# ut_basketball_robot_mainboard_2018.net
KiCad netlist of a schematic drawn in Altium Designer
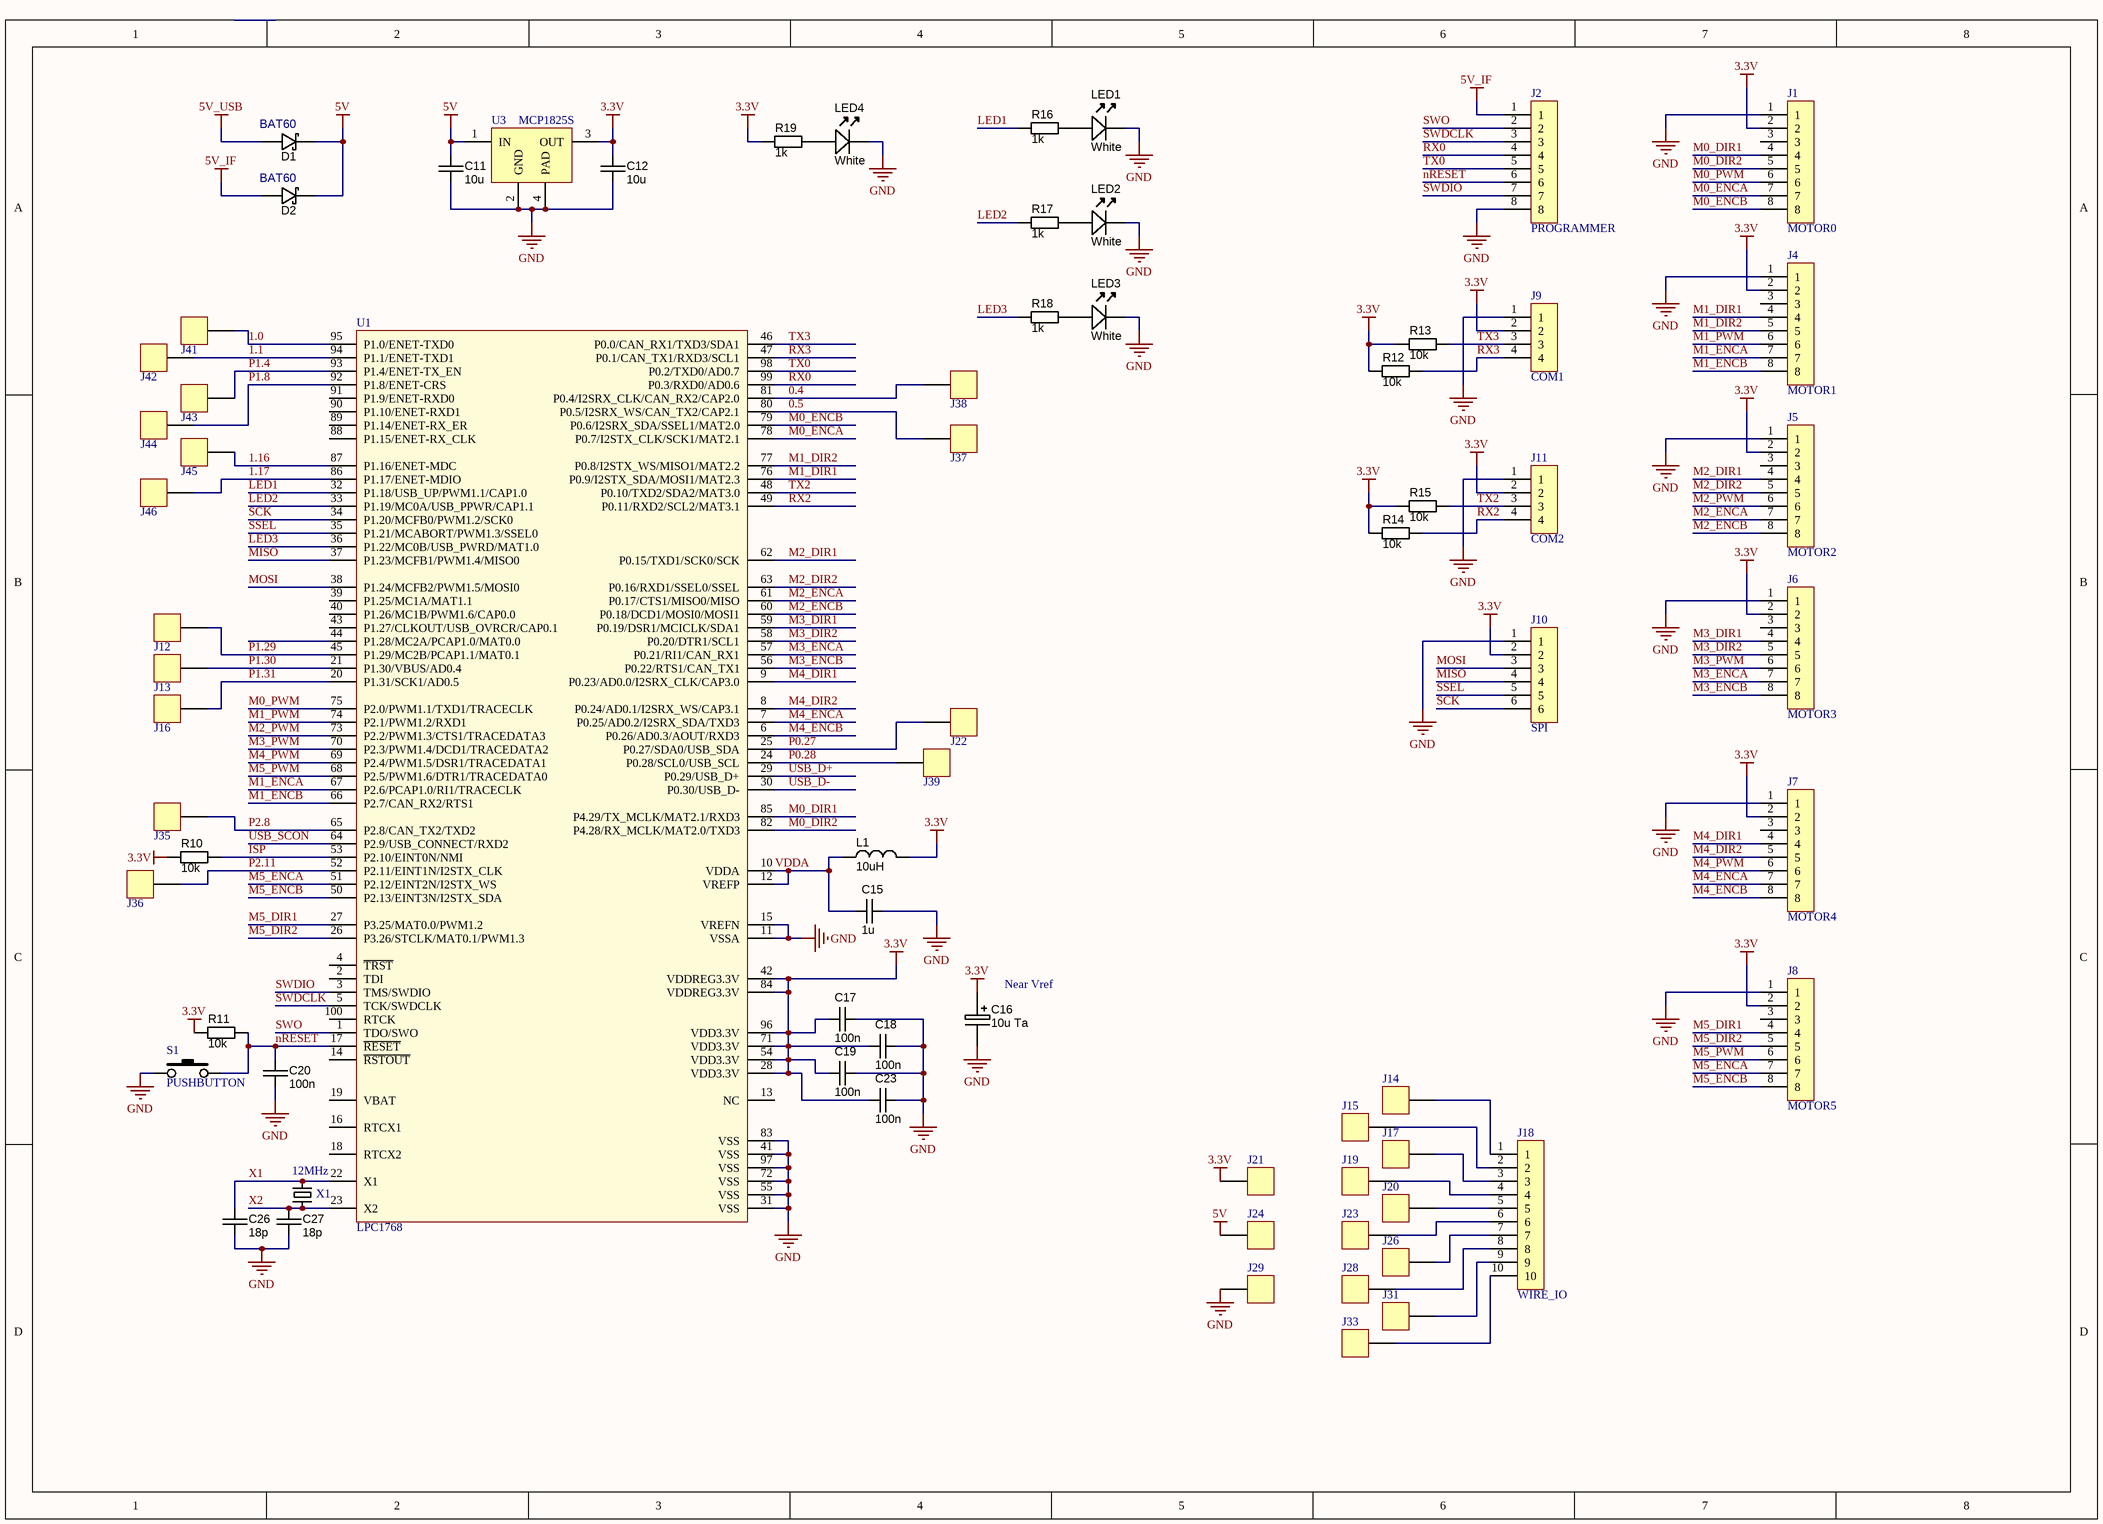
[diagram p0: ut_basketball_robot_mainboard_2018.SchDoc]

(export (version "E")
  (design (tool "Eeschema 10.0.6"))
  (components
    (comp (ref "C11")
      (value "10u")
      (footprint "CAPC3216X180N")
      (description "Capacitor SMD Cer 10uF 10% 10V X5R 1206")
      (fields (field (name "TOLERANCE") "±10%"))
      (libsource (lib "PBL - Capacitors") (part "CAPC_10u_1206_10V"))
    )
    (comp (ref "C12")
      (value "10u")
      (footprint "CAPC3216X180N")
      (description "Capacitor SMD Cer 10uF 10% 10V X5R 1206")
      (fields (field (name "TOLERANCE") "±10%"))
      (libsource (lib "PBL - Capacitors") (part "CAPC_10u_1206_10V"))
    )
    (comp (ref "C15")
      (value "1u")
      (footprint "CAPC1608X90N")
      (description "Capacitor SMD Cer 18pF 2% 100V NP0 0603")
      (fields (field (name "TOLERANCE") "±2%"))
      (libsource (lib "PBL - Capacitors") (part "CAPC_18p_0603_100V"))
    )
    (comp (ref "C16")
      (value "10u Ta")
      (footprint "CAPMP3528X210N")
      (description "Capacitor SMD Tantalum 47uF 20% 6.3V 1210")
      (fields (field (name "TOLERANCE") "±20%"))
      (libsource (lib "PBL - Capacitors") (part "CAPT_47u_1210_6V3"))
    )
    (comp (ref "C17")
      (value "100n")
      (footprint "CAPC1608X90N")
      (description "Capacitor SMD Cer 18pF 2% 100V NP0 0603")
      (fields (field (name "TOLERANCE") "±2%"))
      (libsource (lib "PBL - Capacitors") (part "CAPC_18p_0603_100V"))
    )
    (comp (ref "C18")
      (value "100n")
      (footprint "CAPC1608X90N")
      (description "Capacitor SMD Cer 18pF 2% 100V NP0 0603")
      (fields (field (name "TOLERANCE") "±2%"))
      (libsource (lib "PBL - Capacitors") (part "CAPC_18p_0603_100V"))
    )
    (comp (ref "C19")
      (value "100n")
      (footprint "CAPC1608X90N")
      (description "Capacitor SMD Cer 18pF 2% 100V NP0 0603")
      (fields (field (name "TOLERANCE") "±2%"))
      (libsource (lib "PBL - Capacitors") (part "CAPC_18p_0603_100V"))
    )
    (comp (ref "C20")
      (value "100n")
      (footprint "CAPC1608X90N")
      (description "Capacitor SMD Cer 18pF 2% 100V NP0 0603")
      (fields (field (name "TOLERANCE") "±2%"))
      (libsource (lib "PBL - Capacitors") (part "CAPC_18p_0603_100V"))
    )
    (comp (ref "C23")
      (value "100n")
      (footprint "CAPC1608X90N")
      (description "Capacitor SMD Cer 18pF 2% 100V NP0 0603")
      (fields (field (name "TOLERANCE") "±2%"))
      (libsource (lib "PBL - Capacitors") (part "CAPC_18p_0603_100V"))
    )
    (comp (ref "C26")
      (value "18p")
      (footprint "CAPC1608X90N")
      (description "Capacitor SMD Cer 18pF 2% 100V NP0 0603")
      (fields (field (name "TOLERANCE") "±2%"))
      (libsource (lib "PBL - Capacitors") (part "CAPC_18p_0603_100V"))
    )
    (comp (ref "C27")
      (value "18p")
      (footprint "CAPC1608X90N")
      (description "Capacitor SMD Cer 18pF 2% 100V NP0 0603")
      (fields (field (name "TOLERANCE") "±2%"))
      (libsource (lib "PBL - Capacitors") (part "CAPC_18p_0603_100V"))
    )
    (comp (ref "D1")
      (value "BAT60")
      (footprint "SOD323")
      (description "Diode Schottky SMD 20V 0.5A SOD123")
      (libsource (lib "PBL - Diodes") (part "DIODE_SCHOTTKY_SS0520"))
    )
    (comp (ref "D2")
      (value "BAT60")
      (footprint "SOD323")
      (description "Diode Schottky SMD 20V 0.5A SOD123")
      (libsource (lib "PBL - Diodes") (part "DIODE_SCHOTTKY_SS0520"))
    )
    (comp (ref "J1")
      (value "MOTOR0")
      (footprint "MICRO-MATCH-FOB-08")
      (libsource (lib "connectors_micromatch") (part "HEADER-8"))
    )
    (comp (ref "J2")
      (value "PROGRAMMER")
      (footprint "MICRO-MATCH-FOB-08")
      (libsource (lib "connectors_micromatch") (part "HEADER-8"))
    )
    (comp (ref "J4")
      (value "MOTOR1")
      (footprint "MICRO-MATCH-FOB-08")
      (libsource (lib "connectors_micromatch") (part "HEADER-8"))
    )
    (comp (ref "J5")
      (value "MOTOR2")
      (footprint "MICRO-MATCH-FOB-08")
      (libsource (lib "connectors_micromatch") (part "HEADER-8"))
    )
    (comp (ref "J6")
      (value "MOTOR3")
      (footprint "MICRO-MATCH-FOB-08")
      (libsource (lib "connectors_micromatch") (part "HEADER-8"))
    )
    (comp (ref "J7")
      (value "MOTOR4")
      (footprint "MICRO-MATCH-FOB-08")
      (libsource (lib "connectors_micromatch") (part "HEADER-8"))
    )
    (comp (ref "J8")
      (value "MOTOR5")
      (footprint "MICRO-MATCH-FOB-08")
      (libsource (lib "connectors_micromatch") (part "HEADER-8"))
    )
    (comp (ref "J9")
      (value "COM1")
      (footprint "MICRO-MATCH-FOB-04")
      (libsource (lib "connectors_micromatch") (part "HEADER-4"))
    )
    (comp (ref "J10")
      (value "SPI")
      (footprint "MICRO-MATCH-FOB-06")
      (libsource (lib "connectors_micromatch") (part "HEADER-6"))
    )
    (comp (ref "J11")
      (value "COM2")
      (footprint "MICRO-MATCH-FOB-04")
      (libsource (lib "connectors_micromatch") (part "HEADER-4"))
    )
    (comp (ref "J12")
      (value "HEADER-1")
      (footprint "PAD-1020")
      (libsource (lib "connectors") (part "HEADER-1"))
    )
    (comp (ref "J13")
      (value "HEADER-1")
      (footprint "PAD-1020")
      (libsource (lib "connectors") (part "HEADER-1"))
    )
    (comp (ref "J14")
      (value "HEADER-1")
      (footprint "PAD-1020")
      (libsource (lib "connectors") (part "HEADER-1"))
    )
    (comp (ref "J15")
      (value "HEADER-1")
      (footprint "PAD-1020")
      (libsource (lib "connectors") (part "HEADER-1"))
    )
    (comp (ref "J16")
      (value "HEADER-1")
      (footprint "PAD-1020")
      (libsource (lib "connectors") (part "HEADER-1"))
    )
    (comp (ref "J17")
      (value "HEADER-1")
      (footprint "PAD-1020")
      (libsource (lib "connectors") (part "HEADER-1"))
    )
    (comp (ref "J18")
      (value "WIRE_IO")
      (footprint "MICRO-MATCH-FOB-10")
      (libsource (lib "connectors_micromatch") (part "HEADER-10"))
    )
    (comp (ref "J19")
      (value "HEADER-1")
      (footprint "PAD-1020")
      (libsource (lib "connectors") (part "HEADER-1"))
    )
    (comp (ref "J20")
      (value "HEADER-1")
      (footprint "PAD-1020")
      (libsource (lib "connectors") (part "HEADER-1"))
    )
    (comp (ref "J21") (value "HEADER-1") (footprint "PAD-1020") (libsource (lib "") (part "HEADER-1_1")))
    (comp (ref "J22") (value "HEADER-1") (footprint "PAD-1020") (libsource (lib "") (part "HEADER-1_1")))
    (comp (ref "J23")
      (value "HEADER-1")
      (footprint "PAD-1020")
      (libsource (lib "connectors") (part "HEADER-1"))
    )
    (comp (ref "J24") (value "HEADER-1") (footprint "PAD-1020") (libsource (lib "") (part "HEADER-1_1")))
    (comp (ref "J26")
      (value "HEADER-1")
      (footprint "PAD-1020")
      (libsource (lib "connectors") (part "HEADER-1"))
    )
    (comp (ref "J28")
      (value "HEADER-1")
      (footprint "PAD-1020")
      (libsource (lib "connectors") (part "HEADER-1"))
    )
    (comp (ref "J29") (value "HEADER-1") (footprint "PAD-1020") (libsource (lib "") (part "HEADER-1_1")))
    (comp (ref "J31")
      (value "HEADER-1")
      (footprint "PAD-1020")
      (libsource (lib "connectors") (part "HEADER-1"))
    )
    (comp (ref "J33")
      (value "HEADER-1")
      (footprint "PAD-1020")
      (libsource (lib "connectors") (part "HEADER-1"))
    )
    (comp (ref "J35")
      (value "HEADER-1")
      (footprint "PAD-1020")
      (libsource (lib "connectors") (part "HEADER-1"))
    )
    (comp (ref "J36")
      (value "HEADER-1")
      (footprint "PAD-1020")
      (libsource (lib "connectors") (part "HEADER-1"))
    )
    (comp (ref "J37") (value "HEADER-1") (footprint "PAD-1020") (libsource (lib "") (part "HEADER-1_1")))
    (comp (ref "J38") (value "HEADER-1") (footprint "PAD-1020") (libsource (lib "") (part "HEADER-1_1")))
    (comp (ref "J39") (value "HEADER-1") (footprint "PAD-1020") (libsource (lib "") (part "HEADER-1_1")))
    (comp (ref "J41")
      (value "HEADER-1")
      (footprint "PAD-1020")
      (libsource (lib "connectors") (part "HEADER-1"))
    )
    (comp (ref "J42")
      (value "HEADER-1")
      (footprint "PAD-1020")
      (libsource (lib "connectors") (part "HEADER-1"))
    )
    (comp (ref "J43")
      (value "HEADER-1")
      (footprint "PAD-1020")
      (libsource (lib "connectors") (part "HEADER-1"))
    )
    (comp (ref "J44")
      (value "HEADER-1")
      (footprint "PAD-1020")
      (libsource (lib "connectors") (part "HEADER-1"))
    )
    (comp (ref "J45")
      (value "HEADER-1")
      (footprint "PAD-1020")
      (libsource (lib "connectors") (part "HEADER-1"))
    )
    (comp (ref "J46")
      (value "HEADER-1")
      (footprint "PAD-1020")
      (libsource (lib "connectors") (part "HEADER-1"))
    )
    (comp (ref "L1")
      (value "10uH")
      (footprint "INDC1608N")
      (description "Ferrite bead 120 Ohm at 100 MHz 2A 0603 SMD")
      (libsource (lib "PBL - Inductors") (part "FERRITE_120R-100MHz_0603"))
    )
    (comp (ref "LED1")
      (value "White")
      (footprint "LED-0603-WHITE")
      (description "LED 0603 SMD Bright White 8700K")
      (libsource (lib "PBL - Light Sources") (part "LED_SMD_White_0603_Bright"))
    )
    (comp (ref "LED2")
      (value "White")
      (footprint "LED-0603-WHITE")
      (description "LED 0603 SMD Bright White 8700K")
      (libsource (lib "PBL - Light Sources") (part "LED_SMD_White_0603_Bright"))
    )
    (comp (ref "LED3")
      (value "White")
      (footprint "LED-0603-WHITE")
      (description "LED 0603 SMD Bright White 8700K")
      (libsource (lib "PBL - Light Sources") (part "LED_SMD_White_0603_Bright"))
    )
    (comp (ref "LED4")
      (value "White")
      (footprint "LED-0603-WHITE")
      (description "LED 0603 SMD Bright White 8700K")
      (libsource (lib "PBL - Light Sources") (part "LED_SMD_White_0603_Bright"))
    )
    (comp (ref "R10")
      (value "10k")
      (footprint "RESC1608X55N")
      (description "Resistor SMD chip 10k Ohm 0.1W 5% 0603")
      (fields (field (name "TOLERANCE") "±5%"))
      (libsource (lib "") (part "RES_10K_0603_5%_1"))
    )
    (comp (ref "R11")
      (value "10k")
      (footprint "RESC1608X55N")
      (description "Resistor SMD chip 10k Ohm 0.1W 5% 0603")
      (fields (field (name "TOLERANCE") "±5%"))
      (libsource (lib "PBL - Resistors") (part "RES_10K_0603_5%"))
    )
    (comp (ref "R12")
      (value "10k")
      (footprint "RESC1608X55N")
      (description "Resistor SMD chip 10k Ohm 0.1W 5% 0603")
      (fields (field (name "TOLERANCE") "±5%"))
      (libsource (lib "PBL - Resistors") (part "RES_10K_0603_5%"))
    )
    (comp (ref "R13")
      (value "10k")
      (footprint "RESC1608X55N")
      (description "Resistor SMD chip 10k Ohm 0.1W 5% 0603")
      (fields (field (name "TOLERANCE") "±5%"))
      (libsource (lib "PBL - Resistors") (part "RES_10K_0603_5%"))
    )
    (comp (ref "R14")
      (value "10k")
      (footprint "RESC1608X55N")
      (description "Resistor SMD chip 10k Ohm 0.1W 5% 0603")
      (fields (field (name "TOLERANCE") "±5%"))
      (libsource (lib "PBL - Resistors") (part "RES_10K_0603_5%"))
    )
    (comp (ref "R15")
      (value "10k")
      (footprint "RESC1608X55N")
      (description "Resistor SMD chip 10k Ohm 0.1W 5% 0603")
      (fields (field (name "TOLERANCE") "±5%"))
      (libsource (lib "PBL - Resistors") (part "RES_10K_0603_5%"))
    )
    (comp (ref "R16")
      (value "1k")
      (footprint "RESC1608X55N")
      (description "Resistor SMD chip 120 Ohm 0.1W 5% 0603")
      (fields (field (name "TOLERANCE") "±5%"))
      (libsource (lib "PBL - Resistors") (part "RES_120R_0603_5%"))
    )
    (comp (ref "R17")
      (value "1k")
      (footprint "RESC1608X55N")
      (description "Resistor SMD chip 120 Ohm 0.1W 5% 0603")
      (fields (field (name "TOLERANCE") "±5%"))
      (libsource (lib "PBL - Resistors") (part "RES_120R_0603_5%"))
    )
    (comp (ref "R18")
      (value "1k")
      (footprint "RESC1608X55N")
      (description "Resistor SMD chip 120 Ohm 0.1W 5% 0603")
      (fields (field (name "TOLERANCE") "±5%"))
      (libsource (lib "PBL - Resistors") (part "RES_120R_0603_5%"))
    )
    (comp (ref "R19")
      (value "1k")
      (footprint "RESC1608X55N")
      (description "Resistor SMD chip 120 Ohm 0.1W 5% 0603")
      (fields (field (name "TOLERANCE") "±5%"))
      (libsource (lib "PBL - Resistors") (part "RES_120R_0603_5%"))
    )
    (comp (ref "S1")
      (value "PUSHBUTTON")
      (footprint "KMR421NGLFS")
      (libsource (lib "switches") (part "PUSHBUTTON"))
    )
    (comp (ref "U1") (value "LPC1768") (footprint "LQFP100") (libsource (lib "nxp") (part "LPC1768")))
    (comp (ref "U3")
      (value "MCP1825S")
      (footprint "SOT230P700X180-4N")
      (libsource (lib "power") (part "MIC5239"))
    )
    (comp (ref "X1")
      (value "12MHz")
      (footprint "XTAL-3.2x2.5")
      (libsource (lib "misc") (part "XTAL-3.2X2.5"))
    )
  )
  (nets
    (net (code "1") (name "/0.4") (class "Default")
      (node (ref "J38") (pin "1") (pinfunction "1_1") (pintype "passive"))
      (node (ref "U1") (pin "81") (pinfunction "P0.4/I2SRX_CLK/CAN_RX2/CAP2.0_81") (pintype "passive"))
    )
    (net (code "2") (name "/0.5") (class "Default")
      (node (ref "J37") (pin "1") (pinfunction "1_1") (pintype "passive"))
      (node (ref "U1") (pin "80") (pinfunction "P0.5/I2SRX_WS/CAN_TX2/CAP2.1_80") (pintype "passive"))
    )
    (net (code "3") (name "/1.0") (class "Default")
      (node (ref "J41") (pin "1") (pinfunction "1_1") (pintype "passive"))
      (node (ref "U1") (pin "95") (pinfunction "P1.0/ENET-TXD0_95") (pintype "passive"))
    )
    (net (code "4") (name "/1.1") (class "Default")
      (node (ref "J42") (pin "1") (pinfunction "1_1") (pintype "passive"))
      (node (ref "U1") (pin "94") (pinfunction "P1.1/ENET-TXD1_94") (pintype "passive"))
    )
    (net (code "5") (name "/1.16") (class "Default")
      (node (ref "J45") (pin "1") (pinfunction "1_1") (pintype "passive"))
      (node (ref "U1") (pin "87") (pinfunction "P1.16/ENET-MDC_87") (pintype "passive"))
    )
    (net (code "6") (name "/1.17") (class "Default")
      (node (ref "J46") (pin "1") (pinfunction "1_1") (pintype "passive"))
      (node (ref "U1") (pin "86") (pinfunction "P1.17/ENET-MDIO_86") (pintype "passive"))
    )
    (net (code "7") (name "/ISP") (class "Default")
      (node (ref "R10") (pin "1") (pinfunction "1_1") (pintype "passive"))
      (node (ref "U1") (pin "53") (pinfunction "P2.10/EINT0N/NMI_53") (pintype "passive"))
    )
    (net (code "8") (name "/LED1") (class "Default")
      (node (ref "R16") (pin "2") (pinfunction "2_2") (pintype "passive"))
      (node (ref "U1") (pin "32") (pinfunction "P1.18/USB_UP/PWM1.1/CAP1.0_32") (pintype "passive"))
    )
    (net (code "9") (name "/LED2") (class "Default")
      (node (ref "R17") (pin "2") (pinfunction "2_2") (pintype "passive"))
      (node (ref "U1") (pin "33") (pinfunction "P1.19/MC0A/USB_PPWR/CAP1.1_33") (pintype "passive"))
    )
    (net (code "10") (name "/LED3") (class "Default")
      (node (ref "R18") (pin "2") (pinfunction "2_2") (pintype "passive"))
      (node (ref "U1") (pin "36") (pinfunction "P1.22/MC0B/USB_PWRD/MAT1.0_36") (pintype "passive"))
    )
    (net (code "11") (name "/M0_DIR1") (class "Default")
      (node (ref "J1") (pin "4") (pinfunction "4_4") (pintype "passive"))
      (node (ref "U1") (pin "85") (pinfunction "P4.29/TX_MCLK/MAT2.1/RXD3_85") (pintype "passive"))
    )
    (net (code "12") (name "/M0_DIR2") (class "Default")
      (node (ref "J1") (pin "5") (pinfunction "5_5") (pintype "passive"))
      (node (ref "U1") (pin "82") (pinfunction "P4.28/RX_MCLK/MAT2.0/TXD3_82") (pintype "passive"))
    )
    (net (code "13") (name "/M0_ENCA") (class "Default")
      (node (ref "J1") (pin "7") (pinfunction "7_7") (pintype "passive"))
      (node (ref "U1") (pin "78") (pinfunction "P0.7/I2STX_CLK/SCK1/MAT2.1_78") (pintype "passive"))
    )
    (net (code "14") (name "/M0_ENCB") (class "Default")
      (node (ref "J1") (pin "8") (pinfunction "8_8") (pintype "passive"))
      (node (ref "U1") (pin "79") (pinfunction "P0.6/I2SRX_SDA/SSEL1/MAT2.0_79") (pintype "passive"))
    )
    (net (code "15") (name "/M0_PWM") (class "Default")
      (node (ref "J1") (pin "6") (pinfunction "6_6") (pintype "passive"))
      (node (ref "U1") (pin "75") (pinfunction "P2.0/PWM1.1/TXD1/TRACECLK_75") (pintype "passive"))
    )
    (net (code "16") (name "/M1_DIR1") (class "Default")
      (node (ref "J4") (pin "4") (pinfunction "4_4") (pintype "passive"))
      (node (ref "U1") (pin "76") (pinfunction "P0.9/I2STX_SDA/MOSI1/MAT2.3_76") (pintype "passive"))
    )
    (net (code "17") (name "/M1_DIR2") (class "Default")
      (node (ref "J4") (pin "5") (pinfunction "5_5") (pintype "passive"))
      (node (ref "U1") (pin "77") (pinfunction "P0.8/I2STX_WS/MISO1/MAT2.2_77") (pintype "passive"))
    )
    (net (code "18") (name "/M1_ENCA") (class "Default")
      (node (ref "J4") (pin "7") (pinfunction "7_7") (pintype "passive"))
      (node (ref "U1") (pin "67") (pinfunction "P2.6/PCAP1.0/RI1/TRACECLK_67") (pintype "passive"))
    )
    (net (code "19") (name "/M1_ENCB") (class "Default")
      (node (ref "J4") (pin "8") (pinfunction "8_8") (pintype "passive"))
      (node (ref "U1") (pin "66") (pinfunction "P2.7/CAN_RX2/RTS1_66") (pintype "passive"))
    )
    (net (code "20") (name "/M1_PWM") (class "Default")
      (node (ref "J4") (pin "6") (pinfunction "6_6") (pintype "passive"))
      (node (ref "U1") (pin "74") (pinfunction "P2.1/PWM1.2/RXD1_74") (pintype "passive"))
    )
    (net (code "21") (name "/M2_DIR1") (class "Default")
      (node (ref "J5") (pin "4") (pinfunction "4_4") (pintype "passive"))
      (node (ref "U1") (pin "62") (pinfunction "P0.15/TXD1/SCK0/SCK_62") (pintype "passive"))
    )
    (net (code "22") (name "/M2_DIR2") (class "Default")
      (node (ref "J5") (pin "5") (pinfunction "5_5") (pintype "passive"))
      (node (ref "U1") (pin "63") (pinfunction "P0.16/RXD1/SSEL0/SSEL_63") (pintype "passive"))
    )
    (net (code "23") (name "/M2_ENCA") (class "Default")
      (node (ref "J5") (pin "7") (pinfunction "7_7") (pintype "passive"))
      (node (ref "U1") (pin "61") (pinfunction "P0.17/CTS1/MISO0/MISO_61") (pintype "passive"))
    )
    (net (code "24") (name "/M2_ENCB") (class "Default")
      (node (ref "J5") (pin "8") (pinfunction "8_8") (pintype "passive"))
      (node (ref "U1") (pin "60") (pinfunction "P0.18/DCD1/MOSI0/MOSI1_60") (pintype "passive"))
    )
    (net (code "25") (name "/M2_PWM") (class "Default")
      (node (ref "J5") (pin "6") (pinfunction "6_6") (pintype "passive"))
      (node (ref "U1") (pin "73") (pinfunction "P2.2/PWM1.3/CTS1/TRACEDATA3_73") (pintype "passive"))
    )
    (net (code "26") (name "/M3_DIR1") (class "Default")
      (node (ref "J6") (pin "4") (pinfunction "4_4") (pintype "passive"))
      (node (ref "U1") (pin "59") (pinfunction "P0.19/DSR1/MCICLK/SDA1_59") (pintype "passive"))
    )
    (net (code "27") (name "/M3_DIR2") (class "Default")
      (node (ref "J6") (pin "5") (pinfunction "5_5") (pintype "passive"))
      (node (ref "U1") (pin "58") (pinfunction "P0.20/DTR1/SCL1_58") (pintype "passive"))
    )
    (net (code "28") (name "/M3_ENCA") (class "Default")
      (node (ref "J6") (pin "7") (pinfunction "7_7") (pintype "passive"))
      (node (ref "U1") (pin "57") (pinfunction "P0.21/RI1/CAN_RX1_57") (pintype "passive"))
    )
    (net (code "29") (name "/M3_ENCB") (class "Default")
      (node (ref "J6") (pin "8") (pinfunction "8_8") (pintype "passive"))
      (node (ref "U1") (pin "56") (pinfunction "P0.22/RTS1/CAN_TX1_56") (pintype "passive"))
    )
    (net (code "30") (name "/M3_PWM") (class "Default")
      (node (ref "J6") (pin "6") (pinfunction "6_6") (pintype "passive"))
      (node (ref "U1") (pin "70") (pinfunction "P2.3/PWM1.4/DCD1/TRACEDATA2_70") (pintype "passive"))
    )
    (net (code "31") (name "/M4_DIR1") (class "Default")
      (node (ref "J7") (pin "4") (pinfunction "4_4") (pintype "passive"))
      (node (ref "U1") (pin "9") (pinfunction "P0.23/AD0.0/I2SRX_CLK/CAP3.0_9") (pintype "passive"))
    )
    (net (code "32") (name "/M4_DIR2") (class "Default")
      (node (ref "J7") (pin "5") (pinfunction "5_5") (pintype "passive"))
      (node (ref "U1") (pin "8") (pinfunction "P0.24/AD0.1/I2SRX_WS/CAP3.1_8") (pintype "passive"))
    )
    (net (code "33") (name "/M4_ENCA") (class "Default")
      (node (ref "J7") (pin "7") (pinfunction "7_7") (pintype "passive"))
      (node (ref "U1") (pin "7") (pinfunction "P0.25/AD0.2/I2SRX_SDA/TXD3_7") (pintype "passive"))
    )
    (net (code "34") (name "/M4_ENCB") (class "Default")
      (node (ref "J7") (pin "8") (pinfunction "8_8") (pintype "passive"))
      (node (ref "U1") (pin "6") (pinfunction "P0.26/AD0.3/AOUT/RXD3_6") (pintype "passive"))
    )
    (net (code "35") (name "/M4_PWM") (class "Default")
      (node (ref "J7") (pin "6") (pinfunction "6_6") (pintype "passive"))
      (node (ref "U1") (pin "69") (pinfunction "P2.4/PWM1.5/DSR1/TRACEDATA1_69") (pintype "passive"))
    )
    (net (code "36") (name "/M5_DIR1") (class "Default")
      (node (ref "J8") (pin "4") (pinfunction "4_4") (pintype "passive"))
      (node (ref "U1") (pin "27") (pinfunction "P3.25/MAT0.0/PWM1.2_27") (pintype "passive"))
    )
    (net (code "37") (name "/M5_DIR2") (class "Default")
      (node (ref "J8") (pin "5") (pinfunction "5_5") (pintype "passive"))
      (node (ref "U1") (pin "26") (pinfunction "P3.26/STCLK/MAT0.1/PWM1.3_26") (pintype "passive"))
    )
    (net (code "38") (name "/M5_ENCA") (class "Default")
      (node (ref "J8") (pin "7") (pinfunction "7_7") (pintype "passive"))
      (node (ref "U1") (pin "51") (pinfunction "P2.12/EINT2N/I2STX_WS_51") (pintype "passive"))
    )
    (net (code "39") (name "/M5_ENCB") (class "Default")
      (node (ref "J8") (pin "8") (pinfunction "8_8") (pintype "passive"))
      (node (ref "U1") (pin "50") (pinfunction "P2.13/EINT3N/I2STX_SDA_50") (pintype "passive"))
    )
    (net (code "40") (name "/M5_PWM") (class "Default")
      (node (ref "J8") (pin "6") (pinfunction "6_6") (pintype "passive"))
      (node (ref "U1") (pin "68") (pinfunction "P2.5/PWM1.6/DTR1/TRACEDATA0_68") (pintype "passive"))
    )
    (net (code "41") (name "/MISO") (class "Default")
      (node (ref "J10") (pin "4") (pinfunction "4_4") (pintype "passive"))
      (node (ref "U1") (pin "37") (pinfunction "P1.23/MCFB1/PWM1.4/MISO0_37") (pintype "passive"))
    )
    (net (code "42") (name "/MOSI") (class "Default")
      (node (ref "J10") (pin "3") (pinfunction "3_3") (pintype "passive"))
      (node (ref "U1") (pin "38") (pinfunction "P1.24/MCFB2/PWM1.5/MOSI0_38") (pintype "passive"))
    )
    (net (code "43") (name "/P0.27") (class "Default")
      (node (ref "J22") (pin "1") (pinfunction "1_1") (pintype "passive"))
      (node (ref "U1") (pin "25") (pinfunction "P0.27/SDA0/USB_SDA_25") (pintype "passive"))
    )
    (net (code "44") (name "/P0.28") (class "Default")
      (node (ref "J39") (pin "1") (pinfunction "1_1") (pintype "passive"))
      (node (ref "U1") (pin "24") (pinfunction "P0.28/SCL0/USB_SCL_24") (pintype "passive"))
    )
    (net (code "45") (name "/P1.4") (class "Default")
      (node (ref "J43") (pin "1") (pinfunction "1_1") (pintype "passive"))
      (node (ref "U1") (pin "93") (pinfunction "P1.4/ENET-TX_EN_93") (pintype "passive"))
    )
    (net (code "46") (name "/P1.8") (class "Default")
      (node (ref "J44") (pin "1") (pinfunction "1_1") (pintype "passive"))
      (node (ref "U1") (pin "92") (pinfunction "P1.8/ENET-CRS_92") (pintype "passive"))
    )
    (net (code "47") (name "/P1.29") (class "Default")
      (node (ref "J12") (pin "1") (pinfunction "1_1") (pintype "passive"))
      (node (ref "U1") (pin "45") (pinfunction "P1.29/MC2B/PCAP1.1/MAT0.1_45") (pintype "passive"))
    )
    (net (code "48") (name "/P1.30") (class "Default")
      (node (ref "J13") (pin "1") (pinfunction "1_1") (pintype "passive"))
      (node (ref "U1") (pin "21") (pinfunction "P1.30/VBUS/AD0.4_21") (pintype "passive"))
    )
    (net (code "49") (name "/P1.31") (class "Default")
      (node (ref "J16") (pin "1") (pinfunction "1_1") (pintype "passive"))
      (node (ref "U1") (pin "20") (pinfunction "P1.31/SCK1/AD0.5_20") (pintype "passive"))
    )
    (net (code "50") (name "/P2.8") (class "Default")
      (node (ref "J35") (pin "1") (pinfunction "1_1") (pintype "passive"))
      (node (ref "U1") (pin "65") (pinfunction "P2.8/CAN_TX2/TXD2_65") (pintype "passive"))
    )
    (net (code "51") (name "/P2.11") (class "Default")
      (node (ref "J36") (pin "1") (pinfunction "1_1") (pintype "passive"))
      (node (ref "U1") (pin "52") (pinfunction "P2.11/EINT1N/I2STX_CLK_52") (pintype "passive"))
    )
    (net (code "52") (name "/RX0") (class "Default")
      (node (ref "J2") (pin "4") (pinfunction "4_4") (pintype "passive"))
      (node (ref "U1") (pin "99") (pinfunction "P0.3/RXD0/AD0.6_99") (pintype "passive"))
    )
    (net (code "53") (name "/RX2") (class "Default")
      (node (ref "J11") (pin "4") (pinfunction "4_4") (pintype "passive"))
      (node (ref "R14") (pin "2") (pinfunction "2_2") (pintype "passive"))
      (node (ref "U1") (pin "49") (pinfunction "P0.11/RXD2/SCL2/MAT3.1_49") (pintype "passive"))
    )
    (net (code "54") (name "/RX3") (class "Default")
      (node (ref "J9") (pin "4") (pinfunction "4_4") (pintype "passive"))
      (node (ref "R12") (pin "2") (pinfunction "2_2") (pintype "passive"))
      (node (ref "U1") (pin "47") (pinfunction "P0.1/CAN_TX1/RXD3/SCL1_47") (pintype "passive"))
    )
    (net (code "55") (name "/SCK") (class "Default")
      (node (ref "J10") (pin "6") (pinfunction "6_6") (pintype "passive"))
      (node (ref "U1") (pin "34") (pinfunction "P1.20/MCFB0/PWM1.2/SCK0_34") (pintype "passive"))
    )
    (net (code "56") (name "/SSEL") (class "Default")
      (node (ref "J10") (pin "5") (pinfunction "5_5") (pintype "passive"))
      (node (ref "U1") (pin "35") (pinfunction "P1.21/MCABORT/PWM1.3/SSEL0_35") (pintype "passive"))
    )
    (net (code "57") (name "/SWDCLK") (class "Default")
      (node (ref "J2") (pin "3") (pinfunction "3_3") (pintype "passive"))
      (node (ref "U1") (pin "5") (pinfunction "TCK/SWDCLK_5") (pintype "passive"))
    )
    (net (code "58") (name "/SWDIO") (class "Default")
      (node (ref "J2") (pin "7") (pinfunction "7_7") (pintype "passive"))
      (node (ref "U1") (pin "3") (pinfunction "TMS/SWDIO_3") (pintype "passive"))
    )
    (net (code "59") (name "/SWO") (class "Default")
      (node (ref "J2") (pin "2") (pinfunction "2_2") (pintype "passive"))
      (node (ref "U1") (pin "1") (pinfunction "TDO/SWO_1") (pintype "passive"))
    )
    (net (code "60") (name "/TX0") (class "Default")
      (node (ref "J2") (pin "5") (pinfunction "5_5") (pintype "passive"))
      (node (ref "U1") (pin "98") (pinfunction "P0.2/TXD0/AD0.7_98") (pintype "passive"))
    )
    (net (code "61") (name "/TX2") (class "Default")
      (node (ref "J11") (pin "3") (pinfunction "3_3") (pintype "passive"))
      (node (ref "R15") (pin "2") (pinfunction "2_2") (pintype "passive"))
      (node (ref "U1") (pin "48") (pinfunction "P0.10/TXD2/SDA2/MAT3.0_48") (pintype "passive"))
    )
    (net (code "62") (name "/TX3") (class "Default")
      (node (ref "J9") (pin "3") (pinfunction "3_3") (pintype "passive"))
      (node (ref "R13") (pin "2") (pinfunction "2_2") (pintype "passive"))
      (node (ref "U1") (pin "46") (pinfunction "P0.0/CAN_RX1/TXD3/SDA1_46") (pintype "passive"))
    )
    (net (code "63") (name "/USB_D+") (class "Default")
      (node (ref "U1") (pin "29") (pinfunction "P0.29/USB_D+_29") (pintype "passive"))
    )
    (net (code "64") (name "/USB_D-") (class "Default")
      (node (ref "U1") (pin "30") (pinfunction "P0.30/USB_D-_30") (pintype "passive"))
    )
    (net (code "65") (name "/USB_SCON") (class "Default")
      (node (ref "U1") (pin "64") (pinfunction "P2.9/USB_CONNECT/RXD2_64") (pintype "passive"))
    )
    (net (code "66") (name "/VDDA") (class "Default")
      (node (ref "C15") (pin "1") (pintype "passive"))
      (node (ref "L1") (pin "1") (pinfunction "1_1") (pintype "passive"))
      (node (ref "U1") (pin "10") (pinfunction "VDDA_10") (pintype "passive"))
      (node (ref "U1") (pin "12") (pinfunction "VREFP_12") (pintype "passive"))
    )
    (net (code "67") (name "/X1") (class "Default")
      (node (ref "C26") (pin "1") (pintype "passive"))
      (node (ref "U1") (pin "22") (pinfunction "X1_22") (pintype "passive"))
      (node (ref "X1") (pin "3") (pinfunction "3_3") (pintype "passive"))
    )
    (net (code "68") (name "/X2") (class "Default")
      (node (ref "C27") (pin "1") (pintype "passive"))
      (node (ref "U1") (pin "23") (pinfunction "X2_23") (pintype "passive"))
      (node (ref "X1") (pin "1") (pinfunction "1_1") (pintype "passive"))
    )
    (net (code "69") (name "/nRESET") (class "Default")
      (node (ref "C20") (pin "1") (pintype "passive"))
      (node (ref "J2") (pin "6") (pinfunction "6_6") (pintype "passive"))
      (node (ref "R11") (pin "2") (pinfunction "2_2") (pintype "passive"))
      (node (ref "S1") (pin "2") (pintype "passive"))
      (node (ref "U1") (pin "17") (pinfunction "~{RESET}_17") (pintype "passive"))
    )
    (net (code "70") (name "3.3V") (class "Default")
      (node (ref "C12") (pin "1") (pintype "passive"))
      (node (ref "C16") (pin "1") (pintype "passive"))
      (node (ref "C17") (pin "1") (pintype "passive"))
      (node (ref "C18") (pin "1") (pintype "passive"))
      (node (ref "C19") (pin "1") (pintype "passive"))
      (node (ref "C23") (pin "1") (pintype "passive"))
      (node (ref "J1") (pin "2") (pinfunction "2_2") (pintype "passive"))
      (node (ref "J10") (pin "2") (pinfunction "2_2") (pintype "passive"))
      (node (ref "J11") (pin "2") (pinfunction "2_2") (pintype "passive"))
      (node (ref "J21") (pin "1") (pinfunction "1_1") (pintype "passive"))
      (node (ref "J4") (pin "2") (pinfunction "2_2") (pintype "passive"))
      (node (ref "J5") (pin "2") (pinfunction "2_2") (pintype "passive"))
      (node (ref "J6") (pin "2") (pinfunction "2_2") (pintype "passive"))
      (node (ref "J7") (pin "2") (pinfunction "2_2") (pintype "passive"))
      (node (ref "J8") (pin "2") (pinfunction "2_2") (pintype "passive"))
      (node (ref "J9") (pin "2") (pinfunction "2_2") (pintype "passive"))
      (node (ref "L1") (pin "2") (pinfunction "2_2") (pintype "passive"))
      (node (ref "R10") (pin "2") (pinfunction "2_2") (pintype "passive"))
      (node (ref "R11") (pin "1") (pinfunction "1_1") (pintype "passive"))
      (node (ref "R12") (pin "1") (pinfunction "1_1") (pintype "passive"))
      (node (ref "R13") (pin "1") (pinfunction "1_1") (pintype "passive"))
      (node (ref "R14") (pin "1") (pinfunction "1_1") (pintype "passive"))
      (node (ref "R15") (pin "1") (pinfunction "1_1") (pintype "passive"))
      (node (ref "R19") (pin "2") (pinfunction "2_2") (pintype "passive"))
      (node (ref "U1") (pin "28") (pinfunction "VDD3.3V_28") (pintype "passive"))
      (node (ref "U1") (pin "42") (pinfunction "VDDREG3.3V_42") (pintype "passive"))
      (node (ref "U1") (pin "54") (pinfunction "VDD3.3V_54") (pintype "passive"))
      (node (ref "U1") (pin "71") (pinfunction "VDD3.3V_71") (pintype "passive"))
      (node (ref "U1") (pin "84") (pinfunction "VDDREG3.3V_84") (pintype "passive"))
      (node (ref "U1") (pin "96") (pinfunction "VDD3.3V_96") (pintype "passive"))
      (node (ref "U3") (pin "3") (pinfunction "OUT_3") (pintype "power_in"))
    )
    (net (code "71") (name "5V") (class "Default")
      (node (ref "C11") (pin "1") (pintype "passive"))
      (node (ref "D1") (pin "K") (pinfunction "K_K") (pintype "passive"))
      (node (ref "D2") (pin "K") (pinfunction "K_K") (pintype "passive"))
      (node (ref "J24") (pin "1") (pinfunction "1_1") (pintype "passive"))
      (node (ref "U3") (pin "1") (pinfunction "IN_1") (pintype "power_in"))
    )
    (net (code "72") (name "5V_IF") (class "Default")
      (node (ref "D2") (pin "A") (pinfunction "A_A") (pintype "passive"))
      (node (ref "J2") (pin "1") (pinfunction "1_1") (pintype "passive"))
    )
    (net (code "73") (name "5V_USB") (class "Default")
      (node (ref "D1") (pin "A") (pinfunction "A_A") (pintype "passive"))
    )
    (net (code "74") (name "GND") (class "Default")
      (node (ref "C11") (pin "2") (pintype "passive"))
      (node (ref "C12") (pin "2") (pintype "passive"))
      (node (ref "C15") (pin "2") (pintype "passive"))
      (node (ref "C16") (pin "2") (pintype "passive"))
      (node (ref "C17") (pin "2") (pintype "passive"))
      (node (ref "C18") (pin "2") (pintype "passive"))
      (node (ref "C19") (pin "2") (pintype "passive"))
      (node (ref "C20") (pin "2") (pintype "passive"))
      (node (ref "C23") (pin "2") (pintype "passive"))
      (node (ref "C26") (pin "2") (pintype "passive"))
      (node (ref "C27") (pin "2") (pintype "passive"))
      (node (ref "J1") (pin "1") (pinfunction "1_1") (pintype "passive"))
      (node (ref "J10") (pin "1") (pinfunction "1_1") (pintype "passive"))
      (node (ref "J11") (pin "1") (pinfunction "1_1") (pintype "passive"))
      (node (ref "J2") (pin "8") (pinfunction "8_8") (pintype "passive"))
      (node (ref "J29") (pin "1") (pinfunction "1_1") (pintype "passive"))
      (node (ref "J4") (pin "1") (pinfunction "1_1") (pintype "passive"))
      (node (ref "J5") (pin "1") (pinfunction "1_1") (pintype "passive"))
      (node (ref "J6") (pin "1") (pinfunction "1_1") (pintype "passive"))
      (node (ref "J7") (pin "1") (pinfunction "1_1") (pintype "passive"))
      (node (ref "J8") (pin "1") (pinfunction "1_1") (pintype "passive"))
      (node (ref "J9") (pin "1") (pinfunction "1_1") (pintype "passive"))
      (node (ref "LED1") (pin "K") (pinfunction "K_K") (pintype "passive"))
      (node (ref "LED2") (pin "K") (pinfunction "K_K") (pintype "passive"))
      (node (ref "LED3") (pin "K") (pinfunction "K_K") (pintype "passive"))
      (node (ref "LED4") (pin "K") (pinfunction "K_K") (pintype "passive"))
      (node (ref "S1") (pin "1") (pintype "passive"))
      (node (ref "U1") (pin "11") (pinfunction "VSSA_11") (pintype "passive"))
      (node (ref "U1") (pin "15") (pinfunction "VREFN_15") (pintype "passive"))
      (node (ref "U1") (pin "31") (pinfunction "VSS_31") (pintype "passive"))
      (node (ref "U1") (pin "41") (pinfunction "VSS_41") (pintype "passive"))
      (node (ref "U1") (pin "55") (pinfunction "VSS_55") (pintype "passive"))
      (node (ref "U1") (pin "72") (pinfunction "VSS_72") (pintype "passive"))
      (node (ref "U1") (pin "83") (pinfunction "VSS_83") (pintype "passive"))
      (node (ref "U1") (pin "97") (pinfunction "VSS_97") (pintype "passive"))
      (node (ref "U3") (pin "2") (pinfunction "GND_2") (pintype "power_in"))
      (node (ref "U3") (pin "4") (pinfunction "PAD_4") (pintype "power_in"))
    )
    (net (code "75") (name "Net-(J14-Pad1)") (class "Default")
      (node (ref "J14") (pin "1") (pinfunction "1_1") (pintype "passive"))
      (node (ref "J18") (pin "1") (pinfunction "1_1") (pintype "passive"))
    )
    (net (code "76") (name "Net-(J15-Pad1)") (class "Default")
      (node (ref "J15") (pin "1") (pinfunction "1_1") (pintype "passive"))
      (node (ref "J18") (pin "2") (pinfunction "2_2") (pintype "passive"))
    )
    (net (code "77") (name "Net-(J17-Pad1)") (class "Default")
      (node (ref "J17") (pin "1") (pinfunction "1_1") (pintype "passive"))
      (node (ref "J18") (pin "3") (pinfunction "3_3") (pintype "passive"))
    )
    (net (code "78") (name "Net-(J18-Pad4)") (class "Default")
      (node (ref "J18") (pin "4") (pinfunction "4_4") (pintype "passive"))
      (node (ref "J19") (pin "1") (pinfunction "1_1") (pintype "passive"))
    )
    (net (code "79") (name "Net-(J18-Pad5)") (class "Default")
      (node (ref "J18") (pin "5") (pinfunction "5_5") (pintype "passive"))
      (node (ref "J20") (pin "1") (pinfunction "1_1") (pintype "passive"))
    )
    (net (code "80") (name "Net-(J18-Pad6)") (class "Default")
      (node (ref "J18") (pin "6") (pinfunction "6_6") (pintype "passive"))
      (node (ref "J23") (pin "1") (pinfunction "1_1") (pintype "passive"))
    )
    (net (code "81") (name "Net-(J18-Pad7)") (class "Default")
      (node (ref "J18") (pin "7") (pinfunction "7_7") (pintype "passive"))
      (node (ref "J26") (pin "1") (pinfunction "1_1") (pintype "passive"))
    )
    (net (code "82") (name "Net-(J18-Pad8)") (class "Default")
      (node (ref "J18") (pin "8") (pinfunction "8_8") (pintype "passive"))
      (node (ref "J28") (pin "1") (pinfunction "1_1") (pintype "passive"))
    )
    (net (code "83") (name "Net-(J18-Pad9)") (class "Default")
      (node (ref "J18") (pin "9") (pinfunction "9_9") (pintype "passive"))
      (node (ref "J31") (pin "1") (pinfunction "1_1") (pintype "passive"))
    )
    (net (code "84") (name "Net-(J18-Pad10)") (class "Default")
      (node (ref "J18") (pin "10") (pinfunction "10_10") (pintype "passive"))
      (node (ref "J33") (pin "1") (pinfunction "1_1") (pintype "passive"))
    )
    (net (code "85") (name "Net-(LED1-PadA)") (class "Default")
      (node (ref "LED1") (pin "A") (pinfunction "A_A") (pintype "passive"))
      (node (ref "R16") (pin "1") (pinfunction "1_1") (pintype "passive"))
    )
    (net (code "86") (name "Net-(LED2-PadA)") (class "Default")
      (node (ref "LED2") (pin "A") (pinfunction "A_A") (pintype "passive"))
      (node (ref "R17") (pin "1") (pinfunction "1_1") (pintype "passive"))
    )
    (net (code "87") (name "Net-(LED3-PadA)") (class "Default")
      (node (ref "LED3") (pin "A") (pinfunction "A_A") (pintype "passive"))
      (node (ref "R18") (pin "1") (pinfunction "1_1") (pintype "passive"))
    )
    (net (code "88") (name "Net-(LED4-PadA)") (class "Default")
      (node (ref "LED4") (pin "A") (pinfunction "A_A") (pintype "passive"))
      (node (ref "R19") (pin "1") (pinfunction "1_1") (pintype "passive"))
    )
    (net (code "89") (name "unconnected-(J1-Pad3)") (class "Default")
      (node (ref "J1") (pin "3") (pinfunction "3_3") (pintype "passive"))
    )
    (net (code "90") (name "unconnected-(J4-Pad3)") (class "Default")
      (node (ref "J4") (pin "3") (pinfunction "3_3") (pintype "passive"))
    )
    (net (code "91") (name "unconnected-(J5-Pad3)") (class "Default")
      (node (ref "J5") (pin "3") (pinfunction "3_3") (pintype "passive"))
    )
    (net (code "92") (name "unconnected-(J6-Pad3)") (class "Default")
      (node (ref "J6") (pin "3") (pinfunction "3_3") (pintype "passive"))
    )
    (net (code "93") (name "unconnected-(J7-Pad3)") (class "Default")
      (node (ref "J7") (pin "3") (pinfunction "3_3") (pintype "passive"))
    )
    (net (code "94") (name "unconnected-(J8-Pad3)") (class "Default")
      (node (ref "J8") (pin "3") (pinfunction "3_3") (pintype "passive"))
    )
    (net (code "95") (name "unconnected-(U1-NC-Pad13)") (class "Default")
      (node (ref "U1") (pin "13") (pinfunction "NC_13") (pintype "passive"))
    )
    (net (code "96") (name "unconnected-(U1-P1.9{slash}ENET-RXD0-Pad91)") (class "Default")
      (node (ref "U1") (pin "91") (pinfunction "P1.9/ENET-RXD0_91") (pintype "passive"))
    )
    (net (code "97") (name "unconnected-(U1-P1.10{slash}ENET-RXD1-Pad90)") (class "Default")
      (node (ref "U1") (pin "90") (pinfunction "P1.10/ENET-RXD1_90") (pintype "passive"))
    )
    (net (code "98") (name "unconnected-(U1-P1.14{slash}ENET-RX_ER-Pad89)") (class "Default")
      (node (ref "U1") (pin "89") (pinfunction "P1.14/ENET-RX_ER_89") (pintype "passive"))
    )
    (net (code "99") (name "unconnected-(U1-P1.15{slash}ENET-RX_CLK-Pad88)") (class "Default")
      (node (ref "U1") (pin "88") (pinfunction "P1.15/ENET-RX_CLK_88") (pintype "passive"))
    )
    (net (code "100") (name "unconnected-(U1-P1.25{slash}MC1A{slash}MAT1.1-Pad39)") (class "Default")
      (node (ref "U1") (pin "39") (pinfunction "P1.25/MC1A/MAT1.1_39") (pintype "passive"))
    )
    (net (code "101") (name "unconnected-(U1-P1.26{slash}MC1B{slash}PWM1.6{slash}CAP0.0-Pad40)") (class "Default")
      (node (ref "U1") (pin "40") (pinfunction "P1.26/MC1B/PWM1.6/CAP0.0_40") (pintype "passive"))
    )
    (net (code "102") (name "unconnected-(U1-P1.27{slash}CLKOUT{slash}USB_OVRCR{slash}CAP0.1-Pad43)") (class "Default")
      (node (ref "U1") (pin "43") (pinfunction "P1.27/CLKOUT/USB_OVRCR/CAP0.1_43") (pintype "passive"))
    )
    (net (code "103") (name "unconnected-(U1-P1.28{slash}MC2A{slash}PCAP1.0{slash}MAT0.0-Pad44)") (class "Default")
      (node (ref "U1") (pin "44") (pinfunction "P1.28/MC2A/PCAP1.0/MAT0.0_44") (pintype "passive"))
    )
    (net (code "104") (name "unconnected-(U1-RTCK-Pad100)") (class "Default")
      (node (ref "U1") (pin "100") (pinfunction "RTCK_100") (pintype "passive"))
    )
    (net (code "105") (name "unconnected-(U1-RTCX1-Pad16)") (class "Default")
      (node (ref "U1") (pin "16") (pinfunction "RTCX1_16") (pintype "passive"))
    )
    (net (code "106") (name "unconnected-(U1-RTCX2-Pad18)") (class "Default")
      (node (ref "U1") (pin "18") (pinfunction "RTCX2_18") (pintype "passive"))
    )
    (net (code "107") (name "unconnected-(U1-TDI-Pad2)") (class "Default")
      (node (ref "U1") (pin "2") (pinfunction "TDI_2") (pintype "passive"))
    )
    (net (code "108") (name "unconnected-(U1-VBAT-Pad19)") (class "Default")
      (node (ref "U1") (pin "19") (pinfunction "VBAT_19") (pintype "passive"))
    )
    (net (code "109") (name "unconnected-(U1-~{RSTOUT}-Pad14)") (class "Default")
      (node (ref "U1") (pin "14") (pinfunction "~{RSTOUT}_14") (pintype "passive"))
    )
    (net (code "110") (name "unconnected-(U1-~{TRST}-Pad4)") (class "Default")
      (node (ref "U1") (pin "4") (pinfunction "~{TRST}_4") (pintype "passive"))
    )
  )
)
